# power_shield.net
KiCad netlist of a schematic drawn in EAGLE
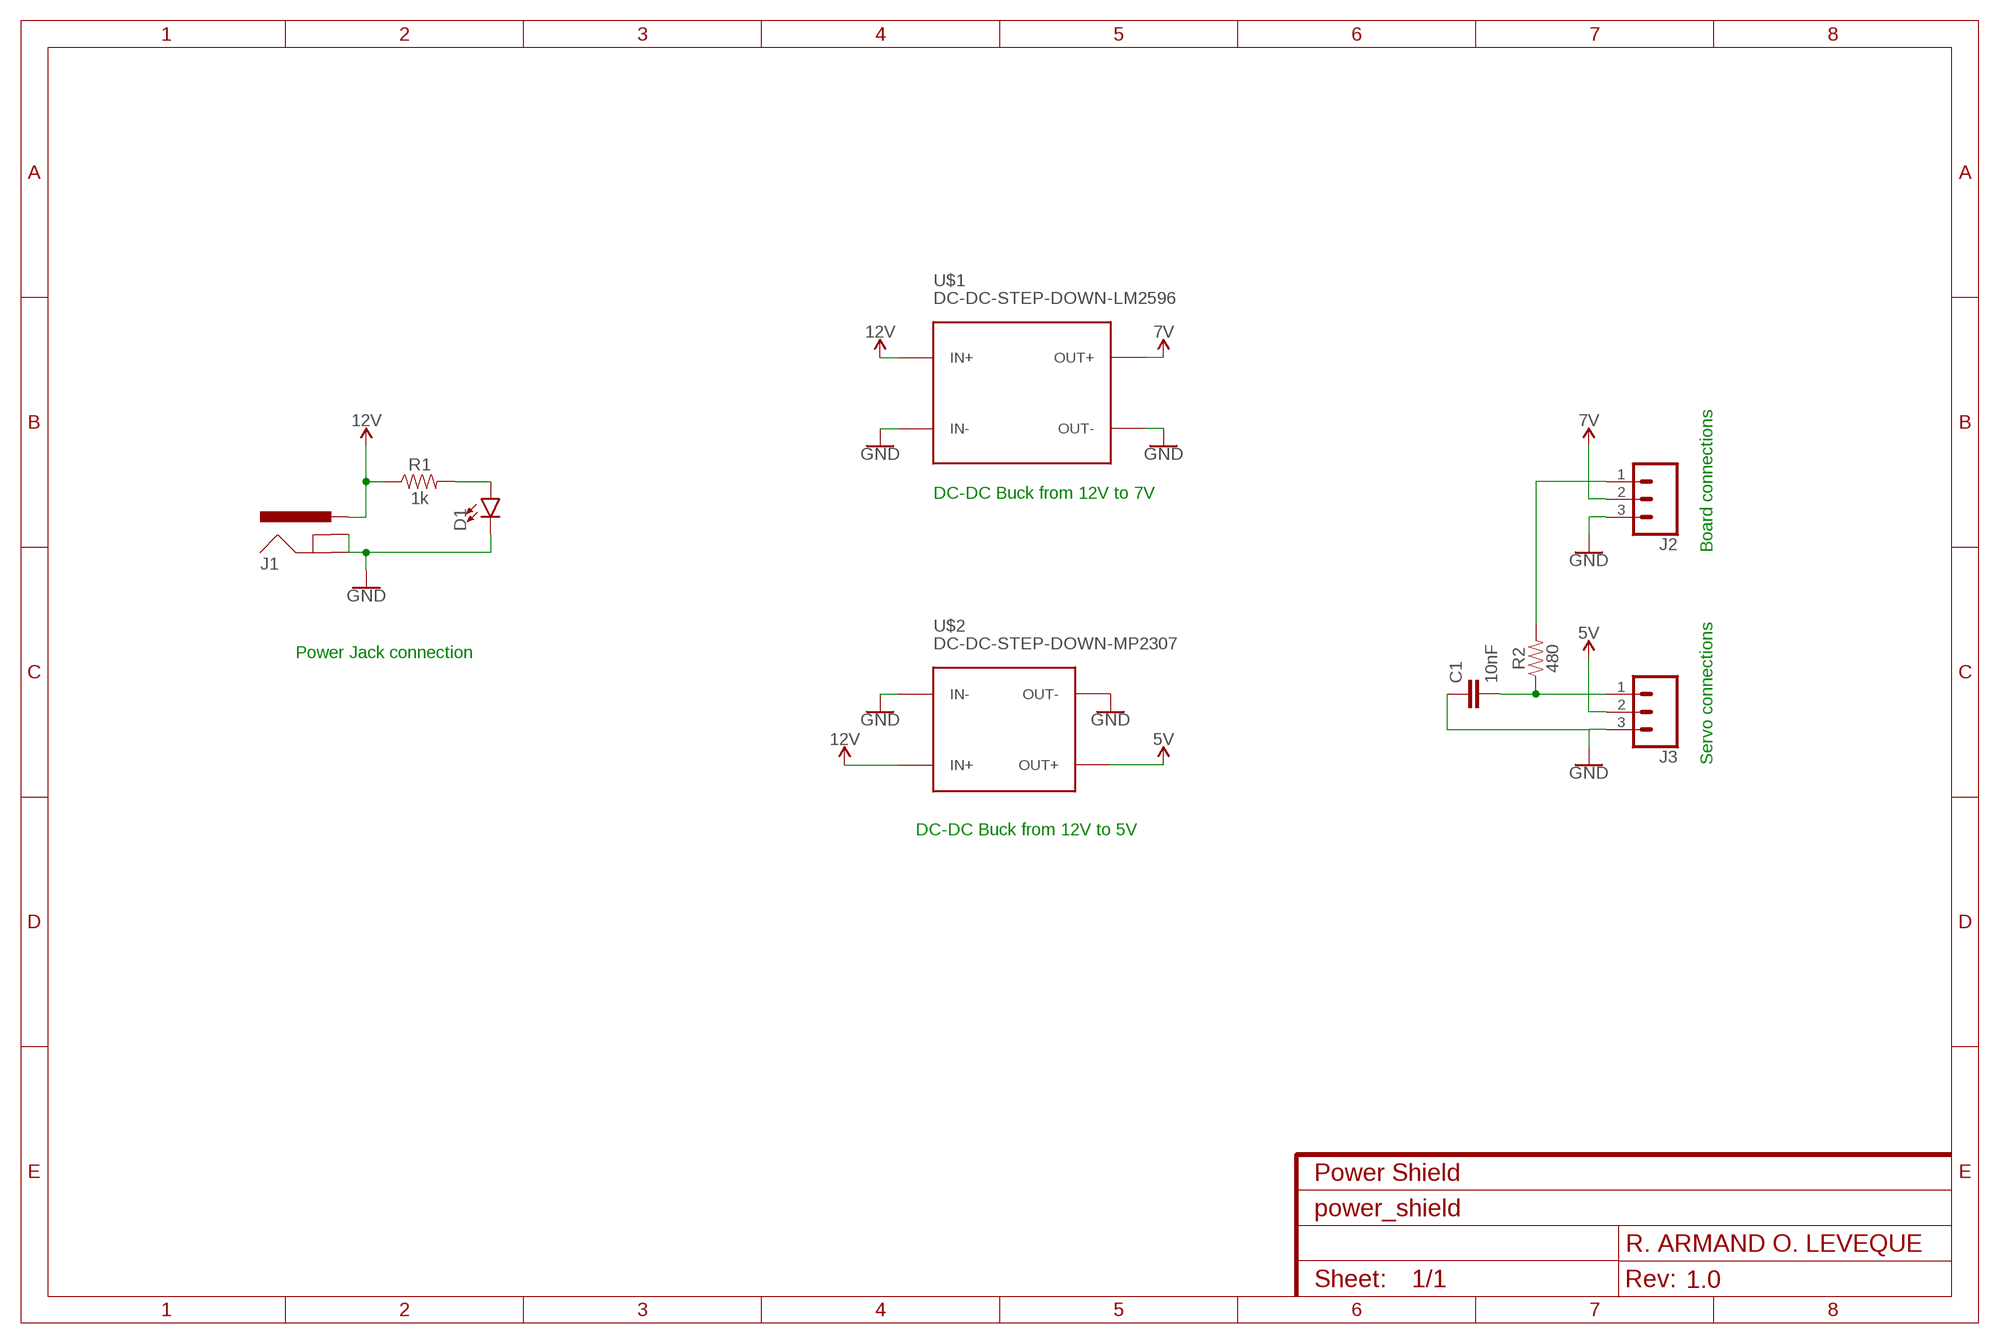
[diagram p0: schematic, sheet 1]

(export (version "E")
  (design (tool "Eeschema 10.0.6"))
  (components
    (comp (ref "C1")
      (value "10nF")
      (footprint "eagle-import:1206")
      (libsource (lib "eagle-import") (part "1.0UF-1206-50V-10%"))
    )
    (comp (ref "D1")
      (value "LED5MM")
      (footprint "eagle-import:LED_5MM")
      (libsource (lib "eagle-import") (part "LED5MM"))
    )
    (comp (ref "J1")
      (value "POWER_JACKPTH_LOCK")
      (footprint "eagle-import:POWER_JACK_PTH_LOCK")
      (libsource (lib "eagle-import") (part "POWER_JACKPTH_LOCK"))
    )
    (comp (ref "J2")
      (value "CONN_03")
      (footprint "eagle-import:1X03")
      (libsource (lib "eagle-import") (part "CONN_03"))
    )
    (comp (ref "J3")
      (value "CONN_03")
      (footprint "eagle-import:1X03")
      (libsource (lib "eagle-import") (part "CONN_03"))
    )
    (comp (ref "R1")
      (value "1k")
      (footprint "eagle-import:1206")
      (libsource (lib "eagle-import") (part "10OHM-1206-1/4W-1%"))
    )
    (comp (ref "R2")
      (value "480")
      (footprint "eagle-import:1206")
      (libsource (lib "eagle-import") (part "10OHM-1206-1/4W-1%"))
    )
    (comp (ref "U$1")
      (value "DC-DC-STEP-DOWN-LM2596")
      (footprint "eagle-import:DC-DC-STEP-DOWN-LM2596")
      (libsource (lib "eagle-import") (part "DC-DC-STEP-DOWN-LM2596"))
    )
    (comp (ref "U$2")
      (value "DC-DC-STEP-DOWN-MP2307")
      (footprint "eagle-import:DC-DC-STEP-DOWN-MP2307")
      (libsource (lib "eagle-import") (part "DC-DC-STEP-DOWN-MP2307"))
    )
  )
  (nets
    (net (code "1") (name "5V") (class "Default")
      (node (ref "J3") (pin "2") (pinfunction "2_2") (pintype "passive"))
      (node (ref "U$2") (pin "OUT+") (pinfunction "OUT+_OUT+") (pintype "bidirectional"))
    )
    (net (code "2") (name "7V") (class "Default")
      (node (ref "J2") (pin "2") (pinfunction "2_2") (pintype "passive"))
      (node (ref "U$1") (pin "OUT+") (pinfunction "OUT+_OUT+") (pintype "bidirectional"))
    )
    (net (code "3") (name "12V") (class "Default")
      (node (ref "J1") (pin "PWR") (pinfunction "PWR_PWR") (pintype "bidirectional"))
      (node (ref "R1") (pin "1") (pinfunction "1_1") (pintype "passive"))
      (node (ref "U$1") (pin "IN+") (pinfunction "IN+_IN+") (pintype "bidirectional"))
      (node (ref "U$2") (pin "IN+") (pinfunction "IN+_IN+") (pintype "bidirectional"))
    )
    (net (code "4") (name "GND") (class "Default")
      (node (ref "C1") (pin "1") (pinfunction "1_1") (pintype "passive"))
      (node (ref "D1") (pin "K") (pinfunction "C_K") (pintype "passive"))
      (node (ref "J1") (pin "GND") (pinfunction "GND_GND") (pintype "bidirectional"))
      (node (ref "J1") (pin "GNDBREAK") (pinfunction "GNDBREAK_GNDBREAK") (pintype "bidirectional"))
      (node (ref "J2") (pin "3") (pinfunction "3_3") (pintype "passive"))
      (node (ref "J3") (pin "3") (pinfunction "3_3") (pintype "passive"))
      (node (ref "U$1") (pin "IN-") (pinfunction "IN-_IN-") (pintype "bidirectional"))
      (node (ref "U$1") (pin "OUT-") (pinfunction "OUT-_OUT-") (pintype "bidirectional"))
      (node (ref "U$2") (pin "IN-") (pinfunction "IN-_IN-") (pintype "bidirectional"))
      (node (ref "U$2") (pin "OUT-") (pinfunction "OUT-_OUT-") (pintype "bidirectional"))
    )
    (net (code "5") (name "Net-(C1-Pad2)") (class "Default")
      (node (ref "C1") (pin "2") (pinfunction "2_2") (pintype "passive"))
      (node (ref "J3") (pin "1") (pinfunction "1_1") (pintype "passive"))
      (node (ref "R2") (pin "1") (pinfunction "1_1") (pintype "passive"))
    )
    (net (code "6") (name "Net-(D1-PadA)") (class "Default")
      (node (ref "D1") (pin "A") (pinfunction "A_A") (pintype "passive"))
      (node (ref "R1") (pin "2") (pinfunction "2_2") (pintype "passive"))
    )
    (net (code "7") (name "Net-(J2-Pad1)") (class "Default")
      (node (ref "J2") (pin "1") (pinfunction "1_1") (pintype "passive"))
      (node (ref "R2") (pin "2") (pinfunction "2_2") (pintype "passive"))
    )
  )
)
